# OSSI-1_Analog_Temp_Module.net
KiCad netlist of a schematic drawn in Altium Designer
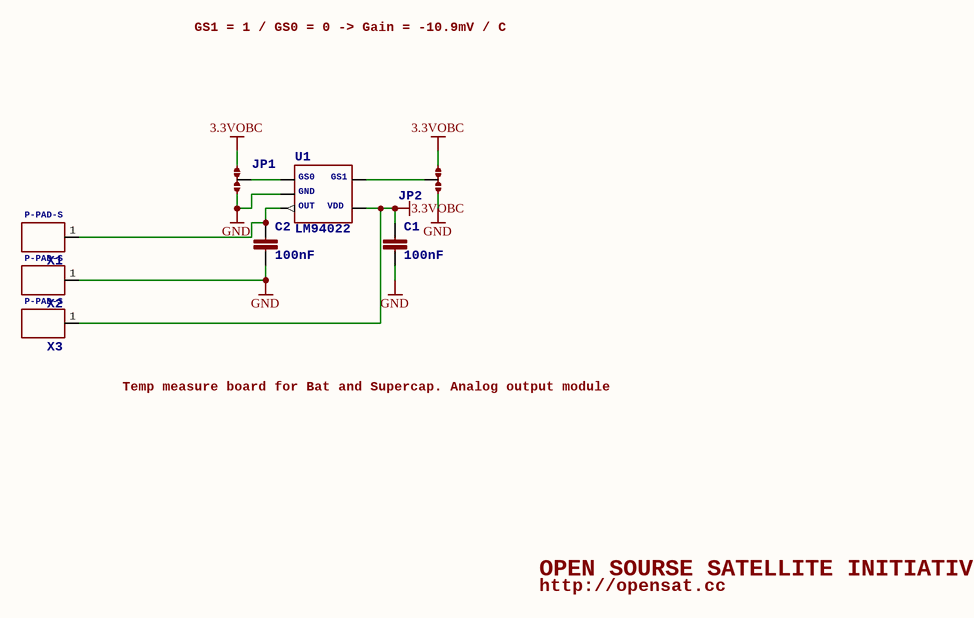
[diagram p0: OSSI-1 Analog Temp Module.SchDoc]

(export (version "E")
  (design (tool "Eeschema 10.0.6"))
  (components
    (comp (ref "C1")
      (value "100nF")
      (footprint "C0603(1608)")
      (fields (field (name ">NAME") "C1") (field (name ">VALUE") "100nF"))
      (libsource (lib "OSSI") (part "C0603(1608)"))
    )
    (comp (ref "C2")
      (value "100nF")
      (footprint "C0603(1608)")
      (fields (field (name ">NAME") "C2") (field (name ">VALUE") "100nF"))
      (libsource (lib "OSSI") (part "C0603(1608)"))
    )
    (comp (ref "JP1")
      (value "JP2")
      (footprint "JP2SMD0603")
      (fields (field (name ">NAME") "JP1"))
      (libsource (lib "OSSI") (part "JP2"))
    )
    (comp (ref "JP2")
      (value "JP2")
      (footprint "JP2SMD0603")
      (fields (field (name ">NAME") "JP2"))
      (libsource (lib "OSSI") (part "JP2"))
    )
    (comp (ref "U1")
      (value "LM94022")
      (footprint "SC70-5")
      (description "LM94022 Temp Sensor From TI")
      (fields
        (field (name "GS0") "GS0")
        (field (name "GND") "GND")
        (field (name "OUT") "OUT")
        (field (name "GS1") "GS1")
        (field (name "VDD") "VDD")
        (field (name ">NAME") "U1")
        (field (name ">VALUE") "LM94022")
      )
      (libsource (lib "OSSI") (part "LM94022"))
    )
    (comp (ref "X1")
      (value "P-PAD-S")
      (footprint "P-PAD-S")
      (fields (field (name ">NAME") "X1") (field (name ">VALUE") "P-PAD-S"))
      (libsource (lib "OSSI") (part "P-PAD-S"))
    )
    (comp (ref "X2")
      (value "P-PAD-S")
      (footprint "P-PAD-S")
      (fields (field (name ">NAME") "X2") (field (name ">VALUE") "P-PAD-S"))
      (libsource (lib "OSSI") (part "P-PAD-S"))
    )
    (comp (ref "X3")
      (value "P-PAD-S")
      (footprint "P-PAD-S")
      (fields (field (name ">NAME") "X3") (field (name ">VALUE") "P-PAD-S"))
      (libsource (lib "OSSI") (part "P-PAD-S"))
    )
  )
  (nets
    (net (code "1") (name "3.3VOBC") (class "Default")
      (node (ref "C1") (pin "1") (pinfunction "1_1") (pintype "passive"))
      (node (ref "JP1") (pin "1") (pinfunction "1_1") (pintype "passive"))
      (node (ref "JP2") (pin "3") (pinfunction "3_3") (pintype "passive"))
      (node (ref "U1") (pin "P$4") (pinfunction "P$4_P$4") (pintype "power_in"))
      (node (ref "X3") (pin "1") (pinfunction "P$1_1") (pintype "passive"))
    )
    (net (code "2") (name "GND") (class "Default")
      (node (ref "C1") (pin "2") (pinfunction "2_2") (pintype "passive"))
      (node (ref "C2") (pin "2") (pinfunction "2_2") (pintype "passive"))
      (node (ref "JP1") (pin "3") (pinfunction "3_3") (pintype "passive"))
      (node (ref "JP2") (pin "1") (pinfunction "1_1") (pintype "passive"))
      (node (ref "U1") (pin "P$2") (pinfunction "P$2_P$2") (pintype "power_in"))
      (node (ref "X2") (pin "1") (pinfunction "P$1_1") (pintype "passive"))
    )
    (net (code "3") (name "Net-(JP1-Pad2)") (class "Default")
      (node (ref "JP1") (pin "2") (pinfunction "2_2") (pintype "passive"))
      (node (ref "U1") (pin "P$1") (pinfunction "P$1_P$1") (pintype "passive"))
    )
    (net (code "4") (name "Net-(JP2-Pad2)") (class "Default")
      (node (ref "JP2") (pin "2") (pinfunction "2_2") (pintype "passive"))
      (node (ref "U1") (pin "P$5") (pinfunction "P$5_P$5") (pintype "passive"))
    )
    (net (code "5") (name "Net-(X1-P$1)") (class "Default")
      (node (ref "C2") (pin "1") (pinfunction "1_1") (pintype "passive"))
      (node (ref "U1") (pin "P$3") (pinfunction "P$3_P$3") (pintype "output"))
      (node (ref "X1") (pin "1") (pinfunction "P$1_1") (pintype "passive"))
    )
  )
)
